# 4GModule-EC2X.net
KiCad netlist of a schematic drawn in Altium Designer
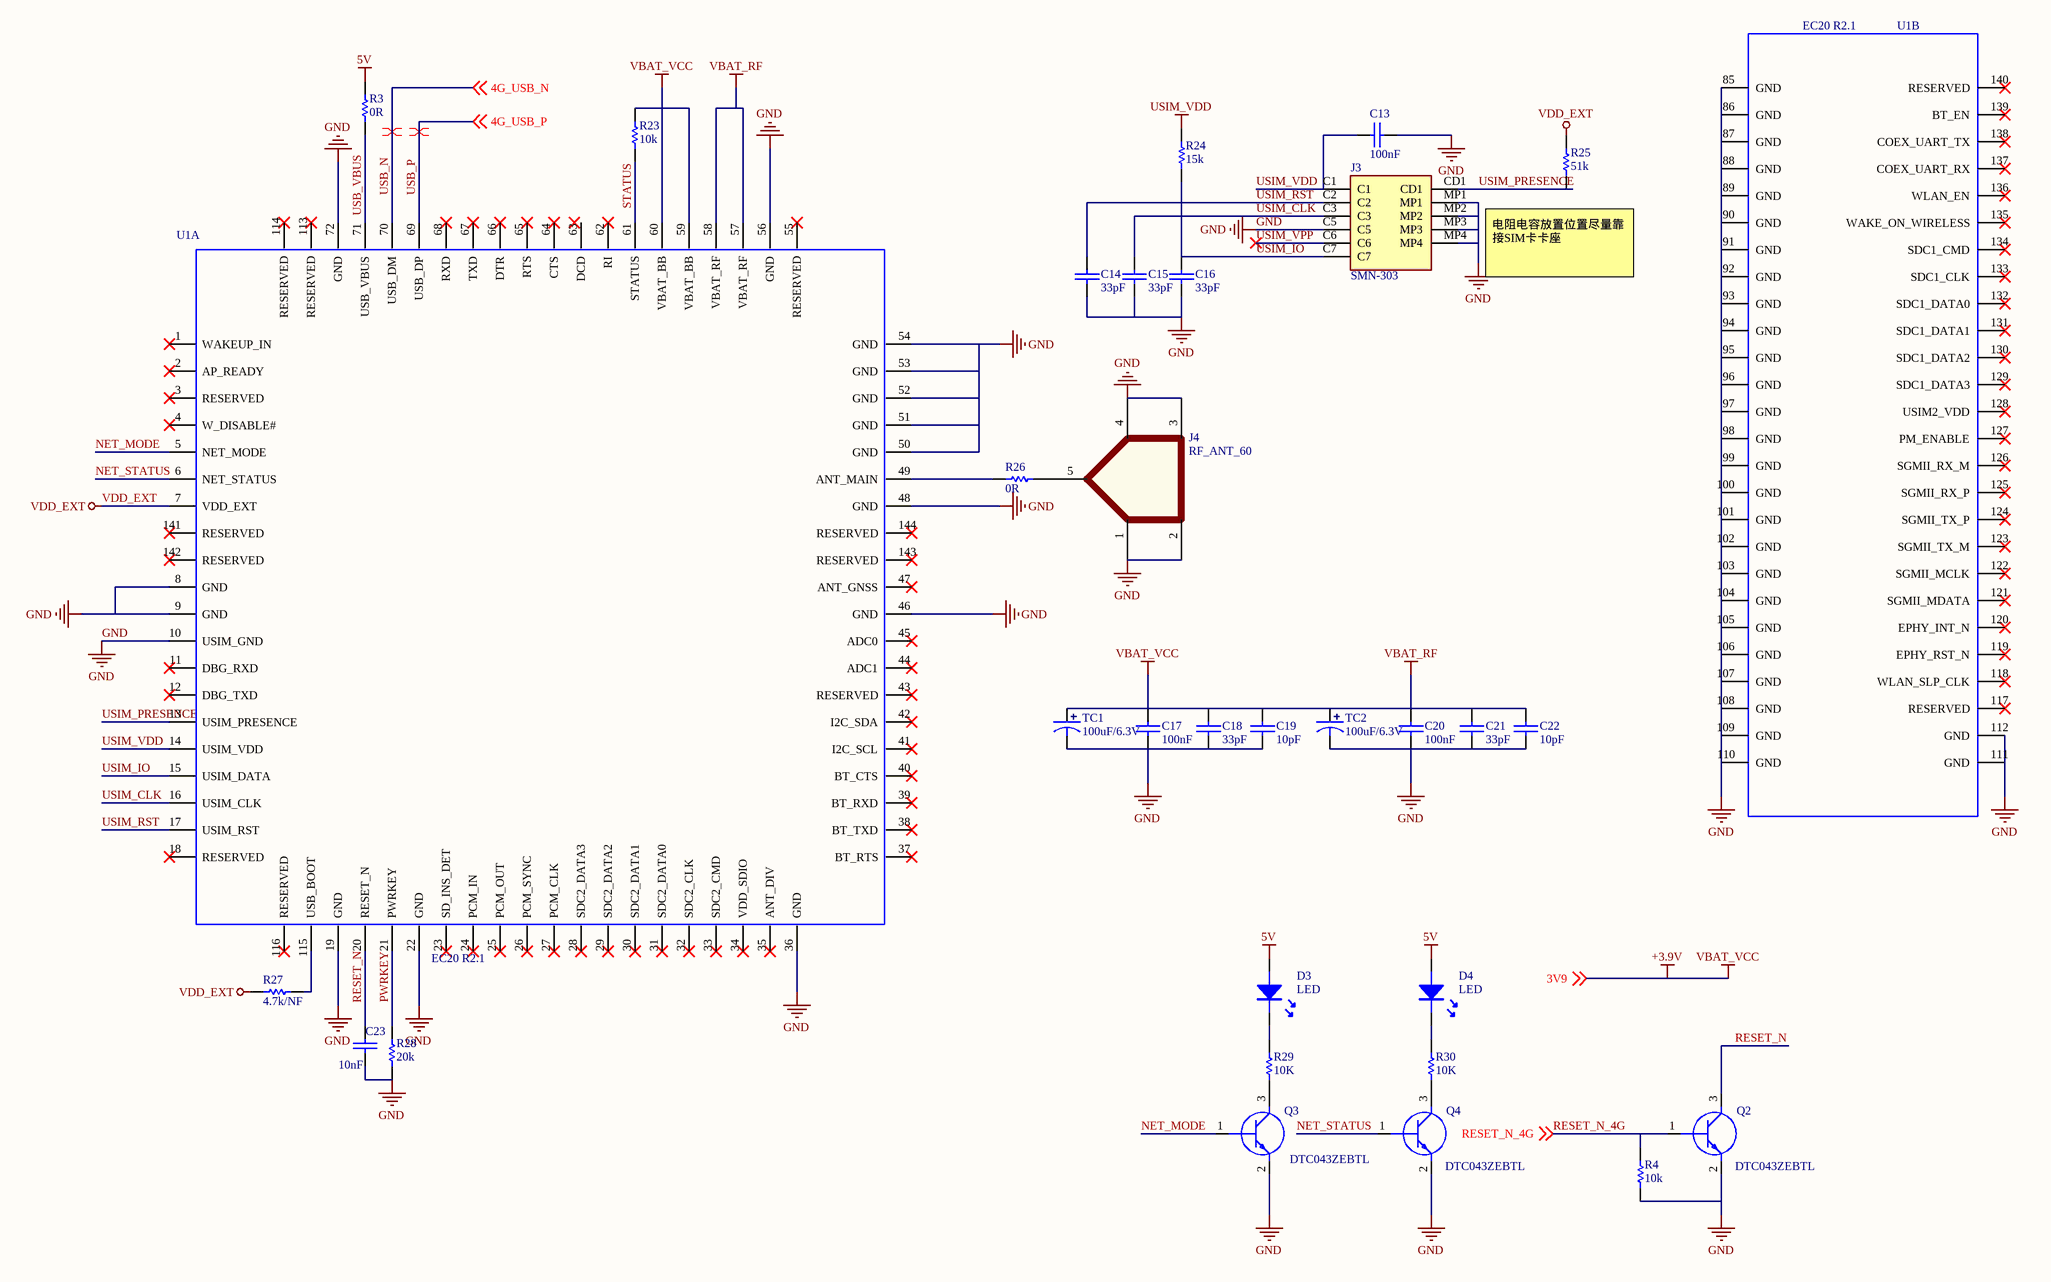
[diagram p0: 4GModule-EC2X.SchDoc]

(export (version "E")
  (design (tool "Eeschema 10.0.6"))
  (components
    (comp (ref "C13")
      (value "100nF")
      (footprint "电容:0402C")
      (description "无极性电容")
      (libsource (lib "电容") (part "CAP"))
    )
    (comp (ref "C14")
      (value "33pF")
      (footprint "电容:0402C")
      (description "无极性电容")
      (libsource (lib "电容") (part "CAP"))
    )
    (comp (ref "C15")
      (value "33pF")
      (footprint "电容:0402C")
      (description "无极性电容")
      (libsource (lib "电容") (part "CAP"))
    )
    (comp (ref "C16")
      (value "33pF")
      (footprint "电容:0402C")
      (description "无极性电容")
      (libsource (lib "电容") (part "CAP"))
    )
    (comp (ref "C17") (value "100nF") (footprint "电容:0402C") (libsource (lib "电容") (part "CAP-NP")))
    (comp (ref "C18") (value "33pF") (footprint "电容:0402C") (libsource (lib "电容") (part "CAP-NP")))
    (comp (ref "C19") (value "10pF") (footprint "电容:0402C") (libsource (lib "电容") (part "CAP-NP")))
    (comp (ref "C20") (value "100nF") (footprint "电容:0402C") (libsource (lib "电容") (part "CAP-NP")))
    (comp (ref "C21") (value "33pF") (footprint "电容:0402C") (libsource (lib "电容") (part "CAP-NP")))
    (comp (ref "C22") (value "10pF") (footprint "电容:0402C") (libsource (lib "电容") (part "CAP-NP")))
    (comp (ref "C23") (value "10nF") (footprint "电容:0402C") (libsource (lib "电容") (part "CAP-NP")))
    (comp (ref "D3")
      (value "LED")
      (footprint "LED-0603W")
      (description "白色")
      (libsource (lib "LED") (part "LED"))
    )
    (comp (ref "D4")
      (value "LED")
      (footprint "LED-0603B")
      (description "蓝色")
      (libsource (lib "LED") (part "LED"))
    )
    (comp (ref "J3")
      (value "SMN-303")
      (footprint "SIM Card:SMN303")
      (description "自弹式NANO SIM卡座 XUNPU(讯普)")
      (libsource (lib "*") (part "SMN-303"))
    )
    (comp (ref "J4")
      (value "RF_ANT_60")
      (footprint "天线座:SMA-EDGE")
      (libsource (lib "天线座") (part "RF_ANT_60"))
    )
    (comp (ref "Q2")
      (value "DTC043ZEBTL")
      (footprint "SamacSys:SOTFL50P160X85-3N")
      (description "Transistor BJT NPN")
      (fields (field (name "MOUSER PART NUMBER") "755-DTC043ZEBTL"))
      (libsource (lib "*") (part "DTC043ZEBTL"))
    )
    (comp (ref "Q3")
      (value "DTC043ZEBTL")
      (footprint "SamacSys:SOTFL50P160X85-3N")
      (description "Transistor BJT NPN")
      (fields (field (name "MOUSER PART NUMBER") "755-DTC043ZEBTL"))
      (libsource (lib "*") (part "DTC043ZEBTL"))
    )
    (comp (ref "Q4")
      (value "DTC043ZEBTL")
      (footprint "SamacSys:SOTFL50P160X85-3N")
      (description "Transistor BJT NPN")
      (fields (field (name "MOUSER PART NUMBER") "755-DTC043ZEBTL"))
      (libsource (lib "*") (part "DTC043ZEBTL"))
    )
    (comp (ref "R3") (value "0R") (footprint "0402R") (libsource (lib "电阻") (part "RES")))
    (comp (ref "R4") (value "10k") (footprint "0402R") (libsource (lib "电阻") (part "RES")))
    (comp (ref "R23") (value "10k") (footprint "0402R") (libsource (lib "电阻") (part "RES")))
    (comp (ref "R24") (value "15k") (footprint "0402R") (libsource (lib "电阻") (part "RES")))
    (comp (ref "R25") (value "51k") (footprint "0402R") (libsource (lib "电阻") (part "RES")))
    (comp (ref "R26") (value "0R") (footprint "0402R") (libsource (lib "电阻") (part "RES")))
    (comp (ref "R27") (value "4.7k/NF") (footprint "0402R") (libsource (lib "电阻") (part "RES")))
    (comp (ref "R28")
      (value "20k")
      (footprint "[01]PCB_ComputerVision2:0402R")
      (libsource (lib "电阻") (part "RES"))
    )
    (comp (ref "R29") (value "10K") (footprint "0402R") (libsource (lib "电阻") (part "RES")))
    (comp (ref "R30") (value "10K") (footprint "0402R") (libsource (lib "电阻") (part "RES")))
    (comp (ref "TC1") (value "100uF/6.3V") (footprint "TAJ-B/3528") (libsource (lib "电容") (part "TCAP")))
    (comp (ref "TC2") (value "100uF/6.3V") (footprint "TAJ-B/3528") (libsource (lib "电容") (part "TCAP")))
    (comp (ref "U1")
      (value "EC20 R2.1")
      (footprint "EC20_R2.1")
      (libsource (lib "SIM Card") (part "EC20 R2.1"))
    )
  )
  (nets
    (net (code "1") (name "+3.9V") (class "Default")
      (node (ref "C17") (pin "2") (pinfunction "2_2") (pintype "passive"))
      (node (ref "C18") (pin "2") (pinfunction "2_2") (pintype "passive"))
      (node (ref "C19") (pin "2") (pinfunction "2_2") (pintype "passive"))
      (node (ref "C20") (pin "2") (pinfunction "2_2") (pintype "passive"))
      (node (ref "C21") (pin "2") (pinfunction "2_2") (pintype "passive"))
      (node (ref "C22") (pin "2") (pinfunction "2_2") (pintype "passive"))
      (node (ref "R23") (pin "2") (pinfunction "2_2") (pintype "passive"))
      (node (ref "TC1") (pin "1") (pinfunction "1_1") (pintype "passive"))
      (node (ref "TC2") (pin "1") (pinfunction "1_1") (pintype "passive"))
      (node (ref "U1") (pin "57") (pinfunction "VBAT_RF_57") (pintype "passive"))
      (node (ref "U1") (pin "58") (pinfunction "VBAT_RF_58") (pintype "passive"))
      (node (ref "U1") (pin "59") (pinfunction "VBAT_BB_59") (pintype "passive"))
      (node (ref "U1") (pin "60") (pinfunction "VBAT_BB_60") (pintype "passive"))
    )
    (net (code "2") (name "/NET_MODE") (class "Default")
      (node (ref "Q3") (pin "1") (pinfunction "B_1") (pintype "passive"))
      (node (ref "U1") (pin "5") (pinfunction "NET_MODE_5") (pintype "passive"))
    )
    (net (code "3") (name "/NET_STATUS") (class "Default")
      (node (ref "Q4") (pin "1") (pinfunction "B_1") (pintype "passive"))
      (node (ref "U1") (pin "6") (pinfunction "NET_STATUS_6") (pintype "passive"))
    )
    (net (code "4") (name "/PWRKEY") (class "Default")
      (node (ref "R28") (pin "2") (pinfunction "2_2") (pintype "passive"))
      (node (ref "U1") (pin "21") (pinfunction "PWRKEY_21") (pintype "passive"))
    )
    (net (code "5") (name "/RESET_N") (class "Default")
      (node (ref "C23") (pin "2") (pinfunction "2_2") (pintype "passive"))
      (node (ref "Q2") (pin "3") (pinfunction "C_3") (pintype "passive"))
      (node (ref "U1") (pin "20") (pinfunction "RESET_N_20") (pintype "passive"))
    )
    (net (code "6") (name "/STATUS") (class "Default")
      (node (ref "R23") (pin "1") (pinfunction "1_1") (pintype "passive"))
      (node (ref "U1") (pin "61") (pinfunction "STATUS_61") (pintype "passive"))
    )
    (net (code "7") (name "/USB_VBUS") (class "Default")
      (node (ref "R3") (pin "1") (pinfunction "1_1") (pintype "passive"))
      (node (ref "U1") (pin "71") (pinfunction "USB_VBUS_71") (pintype "passive"))
    )
    (net (code "8") (name "/USIM_CLK") (class "Default")
      (node (ref "C15") (pin "2") (pinfunction "2_2") (pintype "passive"))
      (node (ref "J3") (pin "C3") (pinfunction "C3_C3") (pintype "passive"))
      (node (ref "U1") (pin "16") (pinfunction "USIM_CLK_16") (pintype "passive"))
    )
    (net (code "9") (name "/USIM_IO") (class "Default")
      (node (ref "C16") (pin "2") (pinfunction "2_2") (pintype "passive"))
      (node (ref "J3") (pin "C7") (pinfunction "C7_C7") (pintype "passive"))
      (node (ref "R24") (pin "1") (pinfunction "1_1") (pintype "passive"))
      (node (ref "U1") (pin "15") (pinfunction "USIM_DATA_15") (pintype "passive"))
    )
    (net (code "10") (name "/USIM_PRESENCE") (class "Default")
      (node (ref "J3") (pin "CD1") (pinfunction "CD1_CD1") (pintype "passive"))
      (node (ref "R25") (pin "1") (pinfunction "1_1") (pintype "passive"))
      (node (ref "U1") (pin "13") (pinfunction "USIM_PRESENCE_13") (pintype "passive"))
    )
    (net (code "11") (name "/USIM_RST") (class "Default")
      (node (ref "C14") (pin "2") (pinfunction "2_2") (pintype "passive"))
      (node (ref "J3") (pin "C2") (pinfunction "C2_C2") (pintype "passive"))
      (node (ref "U1") (pin "17") (pinfunction "USIM_RST_17") (pintype "passive"))
    )
    (net (code "12") (name "/USIM_VPP") (class "Default")
      (node (ref "J3") (pin "C6") (pinfunction "C6_C6") (pintype "passive+no_connect"))
    )
    (net (code "13") (name "4G_USB_N") (class "Default")
      (node (ref "U1") (pin "70") (pinfunction "USB_DM_70") (pintype "passive"))
    )
    (net (code "14") (name "4G_USB_P") (class "Default")
      (node (ref "U1") (pin "69") (pinfunction "USB_DP_69") (pintype "passive"))
    )
    (net (code "15") (name "5V") (class "Default")
      (node (ref "D3") (pin "A") (pinfunction "A_A") (pintype "passive"))
      (node (ref "D4") (pin "A") (pinfunction "A_A") (pintype "passive"))
      (node (ref "R3") (pin "2") (pinfunction "2_2") (pintype "passive"))
    )
    (net (code "16") (name "GND") (class "Default")
      (node (ref "C13") (pin "1") (pinfunction "1_1") (pintype "passive"))
      (node (ref "C14") (pin "1") (pinfunction "1_1") (pintype "passive"))
      (node (ref "C15") (pin "1") (pinfunction "1_1") (pintype "passive"))
      (node (ref "C16") (pin "1") (pinfunction "1_1") (pintype "passive"))
      (node (ref "C17") (pin "1") (pinfunction "1_1") (pintype "passive"))
      (node (ref "C18") (pin "1") (pinfunction "1_1") (pintype "passive"))
      (node (ref "C19") (pin "1") (pinfunction "1_1") (pintype "passive"))
      (node (ref "C20") (pin "1") (pinfunction "1_1") (pintype "passive"))
      (node (ref "C21") (pin "1") (pinfunction "1_1") (pintype "passive"))
      (node (ref "C22") (pin "1") (pinfunction "1_1") (pintype "passive"))
      (node (ref "C23") (pin "1") (pinfunction "1_1") (pintype "passive"))
      (node (ref "J3") (pin "C5") (pinfunction "C5_C5") (pintype "passive"))
      (node (ref "J3") (pin "MP1") (pinfunction "MP1_MP1") (pintype "passive"))
      (node (ref "J3") (pin "MP2") (pinfunction "MP2_MP2") (pintype "passive"))
      (node (ref "J3") (pin "MP3") (pinfunction "MP3_MP3") (pintype "passive"))
      (node (ref "J3") (pin "MP4") (pinfunction "MP4_MP4") (pintype "passive"))
      (node (ref "J4") (pin "1") (pinfunction "1_1") (pintype "passive"))
      (node (ref "J4") (pin "2") (pinfunction "2_2") (pintype "passive"))
      (node (ref "J4") (pin "3") (pinfunction "3_3") (pintype "passive"))
      (node (ref "J4") (pin "4") (pinfunction "4_4") (pintype "passive"))
      (node (ref "Q2") (pin "2") (pinfunction "E_2") (pintype "passive"))
      (node (ref "Q3") (pin "2") (pinfunction "E_2") (pintype "passive"))
      (node (ref "Q4") (pin "2") (pinfunction "E_2") (pintype "passive"))
      (node (ref "R28") (pin "1") (pinfunction "1_1") (pintype "passive"))
      (node (ref "R4") (pin "1") (pinfunction "1_1") (pintype "passive"))
      (node (ref "TC1") (pin "2") (pinfunction "2_2") (pintype "passive"))
      (node (ref "TC2") (pin "2") (pinfunction "2_2") (pintype "passive"))
      (node (ref "U1") (pin "10") (pinfunction "USIM_GND_10") (pintype "passive"))
      (node (ref "U1") (pin "100") (pinfunction "GND_100") (pintype "passive"))
      (node (ref "U1") (pin "101") (pinfunction "GND_101") (pintype "passive"))
      (node (ref "U1") (pin "102") (pinfunction "GND_102") (pintype "passive"))
      (node (ref "U1") (pin "103") (pinfunction "GND_103") (pintype "passive"))
      (node (ref "U1") (pin "104") (pinfunction "GND_104") (pintype "passive"))
      (node (ref "U1") (pin "105") (pinfunction "GND_105") (pintype "passive"))
      (node (ref "U1") (pin "106") (pinfunction "GND_106") (pintype "passive"))
      (node (ref "U1") (pin "107") (pinfunction "GND_107") (pintype "passive"))
      (node (ref "U1") (pin "108") (pinfunction "GND_108") (pintype "passive"))
      (node (ref "U1") (pin "109") (pinfunction "GND_109") (pintype "passive"))
      (node (ref "U1") (pin "110") (pinfunction "GND_110") (pintype "passive"))
      (node (ref "U1") (pin "111") (pinfunction "GND_111") (pintype "passive"))
      (node (ref "U1") (pin "112") (pinfunction "GND_112") (pintype "passive"))
      (node (ref "U1") (pin "19") (pinfunction "GND_19") (pintype "passive"))
      (node (ref "U1") (pin "22") (pinfunction "GND_22") (pintype "passive"))
      (node (ref "U1") (pin "36") (pinfunction "GND_36") (pintype "passive"))
      (node (ref "U1") (pin "46") (pinfunction "GND_46") (pintype "passive"))
      (node (ref "U1") (pin "48") (pinfunction "GND_48") (pintype "passive"))
      (node (ref "U1") (pin "50") (pinfunction "GND_50") (pintype "passive"))
      (node (ref "U1") (pin "51") (pinfunction "GND_51") (pintype "passive"))
      (node (ref "U1") (pin "52") (pinfunction "GND_52") (pintype "passive"))
      (node (ref "U1") (pin "53") (pinfunction "GND_53") (pintype "passive"))
      (node (ref "U1") (pin "54") (pinfunction "GND_54") (pintype "passive"))
      (node (ref "U1") (pin "56") (pinfunction "GND_56") (pintype "passive"))
      (node (ref "U1") (pin "72") (pinfunction "GND_72") (pintype "passive"))
      (node (ref "U1") (pin "8") (pinfunction "GND_8") (pintype "passive"))
      (node (ref "U1") (pin "85") (pinfunction "GND_85") (pintype "passive"))
      (node (ref "U1") (pin "86") (pinfunction "GND_86") (pintype "passive"))
      (node (ref "U1") (pin "87") (pinfunction "GND_87") (pintype "passive"))
      (node (ref "U1") (pin "88") (pinfunction "GND_88") (pintype "passive"))
      (node (ref "U1") (pin "89") (pinfunction "GND_89") (pintype "passive"))
      (node (ref "U1") (pin "9") (pinfunction "GND_9") (pintype "passive"))
      (node (ref "U1") (pin "90") (pinfunction "GND_90") (pintype "passive"))
      (node (ref "U1") (pin "91") (pinfunction "GND_91") (pintype "passive"))
      (node (ref "U1") (pin "92") (pinfunction "GND_92") (pintype "passive"))
      (node (ref "U1") (pin "93") (pinfunction "GND_93") (pintype "passive"))
      (node (ref "U1") (pin "94") (pinfunction "GND_94") (pintype "passive"))
      (node (ref "U1") (pin "95") (pinfunction "GND_95") (pintype "passive"))
      (node (ref "U1") (pin "96") (pinfunction "GND_96") (pintype "passive"))
      (node (ref "U1") (pin "97") (pinfunction "GND_97") (pintype "passive"))
      (node (ref "U1") (pin "98") (pinfunction "GND_98") (pintype "passive"))
      (node (ref "U1") (pin "99") (pinfunction "GND_99") (pintype "passive"))
    )
    (net (code "17") (name "Net-(D3-PadK)") (class "Default")
      (node (ref "D3") (pin "K") (pinfunction "K_K") (pintype "passive"))
      (node (ref "R29") (pin "2") (pinfunction "2_2") (pintype "passive"))
    )
    (net (code "18") (name "Net-(D4-PadK)") (class "Default")
      (node (ref "D4") (pin "K") (pinfunction "K_K") (pintype "passive"))
      (node (ref "R30") (pin "2") (pinfunction "2_2") (pintype "passive"))
    )
    (net (code "19") (name "Net-(J4-Pad5)") (class "Default")
      (node (ref "J4") (pin "5") (pinfunction "5_5") (pintype "passive"))
      (node (ref "R26") (pin "2") (pinfunction "2_2") (pintype "passive"))
    )
    (net (code "20") (name "Net-(Q3-C)") (class "Default")
      (node (ref "Q3") (pin "3") (pinfunction "C_3") (pintype "passive"))
      (node (ref "R29") (pin "1") (pinfunction "1_1") (pintype "passive"))
    )
    (net (code "21") (name "Net-(Q4-C)") (class "Default")
      (node (ref "Q4") (pin "3") (pinfunction "C_3") (pintype "passive"))
      (node (ref "R30") (pin "1") (pinfunction "1_1") (pintype "passive"))
    )
    (net (code "22") (name "Net-(U1A-ANT_MAIN)") (class "Default")
      (node (ref "R26") (pin "1") (pinfunction "1_1") (pintype "passive"))
      (node (ref "U1") (pin "49") (pinfunction "ANT_MAIN_49") (pintype "passive"))
    )
    (net (code "23") (name "Net-(U1A-USB_BOOT)") (class "Default")
      (node (ref "R27") (pin "1") (pinfunction "1_1") (pintype "passive"))
      (node (ref "U1") (pin "115") (pinfunction "USB_BOOT_115") (pintype "passive"))
    )
    (net (code "24") (name "RESET_N_4G") (class "Default")
      (node (ref "Q2") (pin "1") (pinfunction "B_1") (pintype "passive"))
      (node (ref "R4") (pin "2") (pinfunction "2_2") (pintype "passive"))
    )
    (net (code "25") (name "USIM_VDD") (class "Default")
      (node (ref "C13") (pin "2") (pinfunction "2_2") (pintype "passive"))
      (node (ref "J3") (pin "C1") (pinfunction "C1_C1") (pintype "passive"))
      (node (ref "R24") (pin "2") (pinfunction "2_2") (pintype "passive"))
      (node (ref "U1") (pin "14") (pinfunction "USIM_VDD_14") (pintype "passive"))
    )
    (net (code "26") (name "VDD_EXT") (class "Default")
      (node (ref "R25") (pin "2") (pinfunction "2_2") (pintype "passive"))
      (node (ref "R27") (pin "2") (pinfunction "2_2") (pintype "passive"))
      (node (ref "U1") (pin "7") (pinfunction "VDD_EXT_7") (pintype "passive"))
    )
    (net (code "27") (name "unconnected-(U1A-ADC0-Pad45)") (class "Default")
      (node (ref "U1") (pin "45") (pinfunction "ADC0_45") (pintype "passive+no_connect"))
    )
    (net (code "28") (name "unconnected-(U1A-ADC1-Pad44)") (class "Default")
      (node (ref "U1") (pin "44") (pinfunction "ADC1_44") (pintype "passive+no_connect"))
    )
    (net (code "29") (name "unconnected-(U1A-ANT_DIV-Pad35)") (class "Default")
      (node (ref "U1") (pin "35") (pinfunction "ANT_DIV_35") (pintype "passive+no_connect"))
    )
    (net (code "30") (name "unconnected-(U1A-ANT_GNSS-Pad47)") (class "Default")
      (node (ref "U1") (pin "47") (pinfunction "ANT_GNSS_47") (pintype "passive+no_connect"))
    )
    (net (code "31") (name "unconnected-(U1A-AP_READY-Pad2)") (class "Default")
      (node (ref "U1") (pin "2") (pinfunction "AP_READY_2") (pintype "passive+no_connect"))
    )
    (net (code "32") (name "unconnected-(U1A-BT_CTS-Pad40)") (class "Default")
      (node (ref "U1") (pin "40") (pinfunction "BT_CTS_40") (pintype "passive+no_connect"))
    )
    (net (code "33") (name "unconnected-(U1A-BT_RTS-Pad37)") (class "Default")
      (node (ref "U1") (pin "37") (pinfunction "BT_RTS_37") (pintype "passive+no_connect"))
    )
    (net (code "34") (name "unconnected-(U1A-BT_RXD-Pad39)") (class "Default")
      (node (ref "U1") (pin "39") (pinfunction "BT_RXD_39") (pintype "passive+no_connect"))
    )
    (net (code "35") (name "unconnected-(U1A-BT_TXD-Pad38)") (class "Default")
      (node (ref "U1") (pin "38") (pinfunction "BT_TXD_38") (pintype "passive+no_connect"))
    )
    (net (code "36") (name "unconnected-(U1A-CTS-Pad64)") (class "Default")
      (node (ref "U1") (pin "64") (pinfunction "CTS_64") (pintype "passive+no_connect"))
    )
    (net (code "37") (name "unconnected-(U1A-DBG_RXD-Pad11)") (class "Default")
      (node (ref "U1") (pin "11") (pinfunction "DBG_RXD_11") (pintype "passive+no_connect"))
    )
    (net (code "38") (name "unconnected-(U1A-DBG_TXD-Pad12)") (class "Default")
      (node (ref "U1") (pin "12") (pinfunction "DBG_TXD_12") (pintype "passive+no_connect"))
    )
    (net (code "39") (name "unconnected-(U1A-DCD-Pad63)") (class "Default")
      (node (ref "U1") (pin "63") (pinfunction "DCD_63") (pintype "passive"))
    )
    (net (code "40") (name "unconnected-(U1A-DTR-Pad66)") (class "Default")
      (node (ref "U1") (pin "66") (pinfunction "DTR_66") (pintype "passive+no_connect"))
    )
    (net (code "41") (name "unconnected-(U1A-I2C_SCL-Pad41)") (class "Default")
      (node (ref "U1") (pin "41") (pinfunction "I2C_SCL_41") (pintype "passive+no_connect"))
    )
    (net (code "42") (name "unconnected-(U1A-I2C_SDA-Pad42)") (class "Default")
      (node (ref "U1") (pin "42") (pinfunction "I2C_SDA_42") (pintype "passive+no_connect"))
    )
    (net (code "43") (name "unconnected-(U1A-PCM_CLK-Pad27)") (class "Default")
      (node (ref "U1") (pin "27") (pinfunction "PCM_CLK_27") (pintype "passive+no_connect"))
    )
    (net (code "44") (name "unconnected-(U1A-PCM_IN-Pad24)") (class "Default")
      (node (ref "U1") (pin "24") (pinfunction "PCM_IN_24") (pintype "passive+no_connect"))
    )
    (net (code "45") (name "unconnected-(U1A-PCM_OUT-Pad25)") (class "Default")
      (node (ref "U1") (pin "25") (pinfunction "PCM_OUT_25") (pintype "passive+no_connect"))
    )
    (net (code "46") (name "unconnected-(U1A-PCM_SYNC-Pad26)") (class "Default")
      (node (ref "U1") (pin "26") (pinfunction "PCM_SYNC_26") (pintype "passive+no_connect"))
    )
    (net (code "47") (name "unconnected-(U1A-RESERVED-Pad3)") (class "Default")
      (node (ref "U1") (pin "3") (pinfunction "RESERVED_3") (pintype "passive+no_connect"))
    )
    (net (code "48") (name "unconnected-(U1A-RESERVED-Pad18)") (class "Default")
      (node (ref "U1") (pin "18") (pinfunction "RESERVED_18") (pintype "passive+no_connect"))
    )
    (net (code "49") (name "unconnected-(U1A-RESERVED-Pad43)") (class "Default")
      (node (ref "U1") (pin "43") (pinfunction "RESERVED_43") (pintype "passive+no_connect"))
    )
    (net (code "50") (name "unconnected-(U1A-RESERVED-Pad55)") (class "Default")
      (node (ref "U1") (pin "55") (pinfunction "RESERVED_55") (pintype "passive+no_connect"))
    )
    (net (code "51") (name "unconnected-(U1A-RESERVED-Pad113)") (class "Default")
      (node (ref "U1") (pin "113") (pinfunction "RESERVED_113") (pintype "passive+no_connect"))
    )
    (net (code "52") (name "unconnected-(U1A-RESERVED-Pad114)") (class "Default")
      (node (ref "U1") (pin "114") (pinfunction "RESERVED_114") (pintype "passive+no_connect"))
    )
    (net (code "53") (name "unconnected-(U1A-RESERVED-Pad116)") (class "Default")
      (node (ref "U1") (pin "116") (pinfunction "RESERVED_116") (pintype "passive+no_connect"))
    )
    (net (code "54") (name "unconnected-(U1A-RESERVED-Pad141)") (class "Default")
      (node (ref "U1") (pin "141") (pinfunction "RESERVED_141") (pintype "passive+no_connect"))
    )
    (net (code "55") (name "unconnected-(U1A-RESERVED-Pad142)") (class "Default")
      (node (ref "U1") (pin "142") (pinfunction "RESERVED_142") (pintype "passive+no_connect"))
    )
    (net (code "56") (name "unconnected-(U1A-RESERVED-Pad143)") (class "Default")
      (node (ref "U1") (pin "143") (pinfunction "RESERVED_143") (pintype "passive+no_connect"))
    )
    (net (code "57") (name "unconnected-(U1A-RESERVED-Pad144)") (class "Default")
      (node (ref "U1") (pin "144") (pinfunction "RESERVED_144") (pintype "passive+no_connect"))
    )
    (net (code "58") (name "unconnected-(U1A-RI-Pad62)") (class "Default")
      (node (ref "U1") (pin "62") (pinfunction "RI_62") (pintype "passive+no_connect"))
    )
    (net (code "59") (name "unconnected-(U1A-RTS-Pad65)") (class "Default")
      (node (ref "U1") (pin "65") (pinfunction "RTS_65") (pintype "passive+no_connect"))
    )
    (net (code "60") (name "unconnected-(U1A-RXD-Pad68)") (class "Default")
      (node (ref "U1") (pin "68") (pinfunction "RXD_68") (pintype "passive+no_connect"))
    )
    (net (code "61") (name "unconnected-(U1A-SDC2_CLK-Pad32)") (class "Default")
      (node (ref "U1") (pin "32") (pinfunction "SDC2_CLK_32") (pintype "passive+no_connect"))
    )
    (net (code "62") (name "unconnected-(U1A-SDC2_CMD-Pad33)") (class "Default")
      (node (ref "U1") (pin "33") (pinfunction "SDC2_CMD_33") (pintype "passive+no_connect"))
    )
    (net (code "63") (name "unconnected-(U1A-SDC2_DATA0-Pad31)") (class "Default")
      (node (ref "U1") (pin "31") (pinfunction "SDC2_DATA0_31") (pintype "passive+no_connect"))
    )
    (net (code "64") (name "unconnected-(U1A-SDC2_DATA1-Pad30)") (class "Default")
      (node (ref "U1") (pin "30") (pinfunction "SDC2_DATA1_30") (pintype "passive+no_connect"))
    )
    (net (code "65") (name "unconnected-(U1A-SDC2_DATA2-Pad29)") (class "Default")
      (node (ref "U1") (pin "29") (pinfunction "SDC2_DATA2_29") (pintype "passive+no_connect"))
    )
    (net (code "66") (name "unconnected-(U1A-SDC2_DATA3-Pad28)") (class "Default")
      (node (ref "U1") (pin "28") (pinfunction "SDC2_DATA3_28") (pintype "passive+no_connect"))
    )
    (net (code "67") (name "unconnected-(U1A-SD_INS_DET-Pad23)") (class "Default")
      (node (ref "U1") (pin "23") (pinfunction "SD_INS_DET_23") (pintype "passive+no_connect"))
    )
    (net (code "68") (name "unconnected-(U1A-TXD-Pad67)") (class "Default")
      (node (ref "U1") (pin "67") (pinfunction "TXD_67") (pintype "passive+no_connect"))
    )
    (net (code "69") (name "unconnected-(U1A-VDD_SDIO-Pad34)") (class "Default")
      (node (ref "U1") (pin "34") (pinfunction "VDD_SDIO_34") (pintype "passive+no_connect"))
    )
    (net (code "70") (name "unconnected-(U1A-WAKEUP_IN-Pad1)") (class "Default")
      (node (ref "U1") (pin "1") (pinfunction "WAKEUP_IN_1") (pintype "passive+no_connect"))
    )
    (net (code "71") (name "unconnected-(U1A-W_DISABLE#-Pad4)") (class "Default")
      (node (ref "U1") (pin "4") (pinfunction "W_DISABLE#_4") (pintype "passive+no_connect"))
    )
    (net (code "72") (name "unconnected-(U1B-BT_EN-Pad139)") (class "Default")
      (node (ref "U1") (pin "139") (pinfunction "BT_EN_139") (pintype "passive+no_connect"))
    )
    (net (code "73") (name "unconnected-(U1B-COEX_UART_RX-Pad137)") (class "Default")
      (node (ref "U1") (pin "137") (pinfunction "COEX_UART_RX_137") (pintype "passive+no_connect"))
    )
    (net (code "74") (name "unconnected-(U1B-COEX_UART_TX-Pad138)") (class "Default")
      (node (ref "U1") (pin "138") (pinfunction "COEX_UART_TX_138") (pintype "passive+no_connect"))
    )
    (net (code "75") (name "unconnected-(U1B-EPHY_INT_N-Pad120)") (class "Default")
      (node (ref "U1") (pin "120") (pinfunction "EPHY_INT_N_120") (pintype "passive+no_connect"))
    )
    (net (code "76") (name "unconnected-(U1B-EPHY_RST_N-Pad119)") (class "Default")
      (node (ref "U1") (pin "119") (pinfunction "EPHY_RST_N_119") (pintype "passive+no_connect"))
    )
    (net (code "77") (name "unconnected-(U1B-PM_ENABLE-Pad127)") (class "Default")
      (node (ref "U1") (pin "127") (pinfunction "PM_ENABLE_127") (pintype "passive+no_connect"))
    )
    (net (code "78") (name "unconnected-(U1B-RESERVED-Pad117)") (class "Default")
      (node (ref "U1") (pin "117") (pinfunction "RESERVED_117") (pintype "passive+no_connect"))
    )
    (net (code "79") (name "unconnected-(U1B-RESERVED-Pad140)") (class "Default")
      (node (ref "U1") (pin "140") (pinfunction "RESERVED_140") (pintype "passive+no_connect"))
    )
    (net (code "80") (name "unconnected-(U1B-SDC1_CLK-Pad133)") (class "Default")
      (node (ref "U1") (pin "133") (pinfunction "SDC1_CLK_133") (pintype "passive+no_connect"))
    )
    (net (code "81") (name "unconnected-(U1B-SDC1_CMD-Pad134)") (class "Default")
      (node (ref "U1") (pin "134") (pinfunction "SDC1_CMD_134") (pintype "passive+no_connect"))
    )
    (net (code "82") (name "unconnected-(U1B-SDC1_DATA0-Pad132)") (class "Default")
      (node (ref "U1") (pin "132") (pinfunction "SDC1_DATA0_132") (pintype "passive+no_connect"))
    )
    (net (code "83") (name "unconnected-(U1B-SDC1_DATA1-Pad131)") (class "Default")
      (node (ref "U1") (pin "131") (pinfunction "SDC1_DATA1_131") (pintype "passive+no_connect"))
    )
    (net (code "84") (name "unconnected-(U1B-SDC1_DATA2-Pad130)") (class "Default")
      (node (ref "U1") (pin "130") (pinfunction "SDC1_DATA2_130") (pintype "passive+no_connect"))
    )
    (net (code "85") (name "unconnected-(U1B-SDC1_DATA3-Pad129)") (class "Default")
      (node (ref "U1") (pin "129") (pinfunction "SDC1_DATA3_129") (pintype "passive+no_connect"))
    )
    (net (code "86") (name "unconnected-(U1B-SGMII_MCLK-Pad122)") (class "Default")
      (node (ref "U1") (pin "122") (pinfunction "SGMII_MCLK_122") (pintype "passive+no_connect"))
    )
    (net (code "87") (name "unconnected-(U1B-SGMII_MDATA-Pad121)") (class "Default")
      (node (ref "U1") (pin "121") (pinfunction "SGMII_MDATA_121") (pintype "passive+no_connect"))
    )
    (net (code "88") (name "unconnected-(U1B-SGMII_RX_M-Pad126)") (class "Default")
      (node (ref "U1") (pin "126") (pinfunction "SGMII_RX_M_126") (pintype "passive+no_connect"))
    )
    (net (code "89") (name "unconnected-(U1B-SGMII_RX_P-Pad125)") (class "Default")
      (node (ref "U1") (pin "125") (pinfunction "SGMII_RX_P_125") (pintype "passive+no_connect"))
    )
    (net (code "90") (name "unconnected-(U1B-SGMII_TX_M-Pad123)") (class "Default")
      (node (ref "U1") (pin "123") (pinfunction "SGMII_TX_M_123") (pintype "passive+no_connect"))
    )
    (net (code "91") (name "unconnected-(U1B-SGMII_TX_P-Pad124)") (class "Default")
      (node (ref "U1") (pin "124") (pinfunction "SGMII_TX_P_124") (pintype "passive+no_connect"))
    )
    (net (code "92") (name "unconnected-(U1B-USIM2_VDD-Pad128)") (class "Default")
      (node (ref "U1") (pin "128") (pinfunction "USIM2_VDD_128") (pintype "passive+no_connect"))
    )
    (net (code "93") (name "unconnected-(U1B-WAKE_ON_WIRELESS-Pad135)") (class "Default")
      (node (ref "U1") (pin "135") (pinfunction "WAKE_ON_WIRELESS_135") (pintype "passive+no_connect"))
    )
    (net (code "94") (name "unconnected-(U1B-WLAN_EN-Pad136)") (class "Default")
      (node (ref "U1") (pin "136") (pinfunction "WLAN_EN_136") (pintype "passive+no_connect"))
    )
    (net (code "95") (name "unconnected-(U1B-WLAN_SLP_CLK-Pad118)") (class "Default")
      (node (ref "U1") (pin "118") (pinfunction "WLAN_SLP_CLK_118") (pintype "passive+no_connect"))
    )
  )
)
